# Arduino_PyunPyun.net
KiCad netlist of a schematic drawn in EAGLE
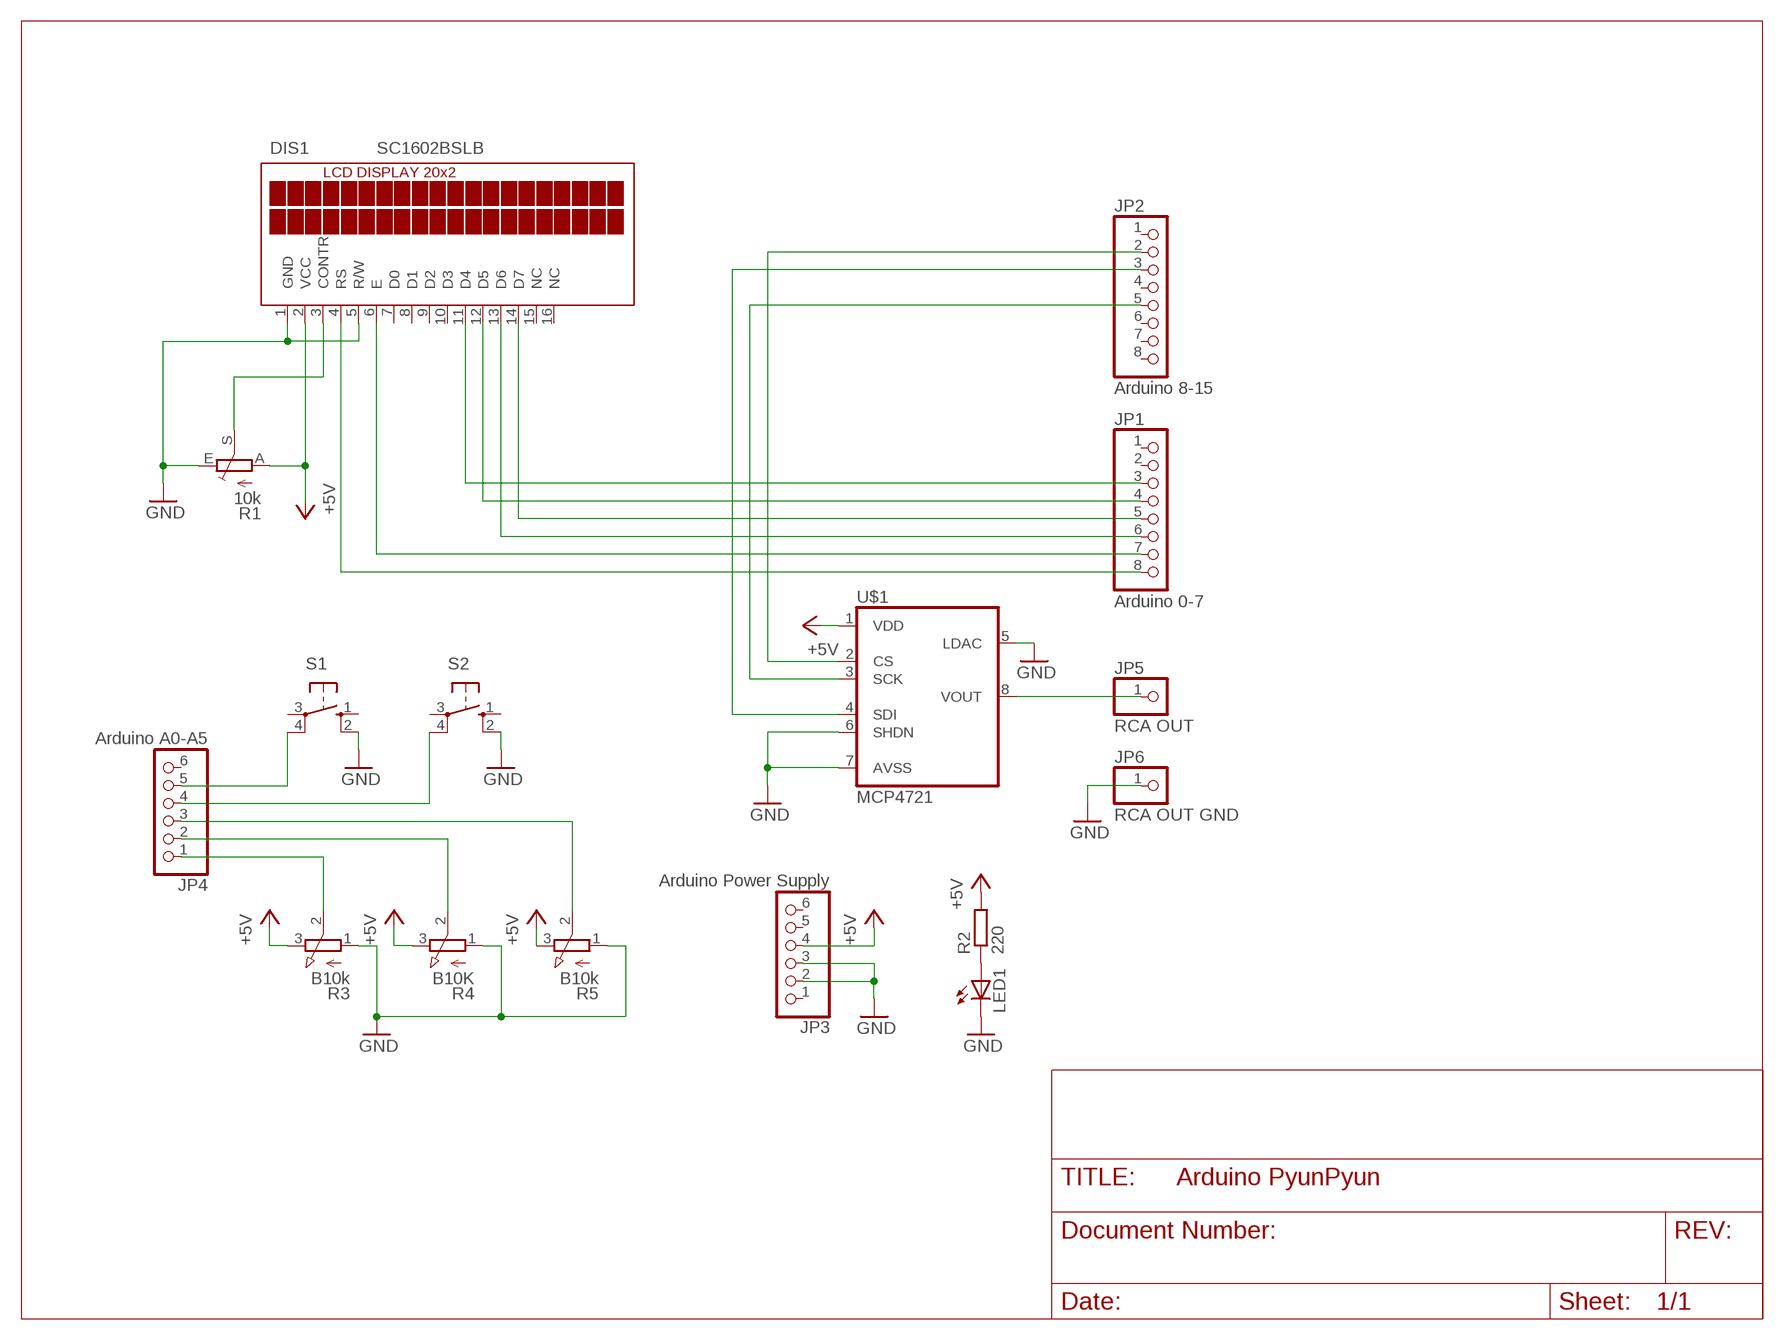
[diagram p0: schematic, sheet 1]

(export (version "E")
  (design (tool "Eeschema 10.0.6"))
  (components
    (comp (ref "DIS1")
      (value "SC1602BSLB")
      (footprint "eagle-import:TUXGR_20X2")
      (libsource (lib "eagle-import") (part "TUXGR_20X2"))
    )
    (comp (ref "JP1")
      (value "Arduino 0-7")
      (footprint "eagle-import:1X08")
      (libsource (lib "eagle-import") (part "PINHD-1X8"))
    )
    (comp (ref "JP2")
      (value "Arduino 8-15")
      (footprint "eagle-import:1X08")
      (libsource (lib "eagle-import") (part "PINHD-1X8"))
    )
    (comp (ref "JP3")
      (value "Arduino Power Supply")
      (footprint "eagle-import:1X06")
      (libsource (lib "eagle-import") (part "PINHD-1X6"))
    )
    (comp (ref "JP4")
      (value "Arduino A0-A5")
      (footprint "eagle-import:1X06")
      (libsource (lib "eagle-import") (part "PINHD-1X6"))
    )
    (comp (ref "JP5")
      (value "RCA OUT")
      (footprint "eagle-import:1X01")
      (libsource (lib "eagle-import") (part "PINHD-1X1"))
    )
    (comp (ref "JP6")
      (value "RCA OUT GND")
      (footprint "eagle-import:1X01")
      (libsource (lib "eagle-import") (part "PINHD-1X1"))
    )
    (comp (ref "LED1")
      (value "LED5MM")
      (footprint "eagle-import:LED5MM")
      (libsource (lib "eagle-import") (part "LED5MM"))
    )
    (comp (ref "R1")
      (value "10k")
      (footprint "eagle-import:B25P")
      (libsource (lib "eagle-import") (part "TRIM_EU-B25P"))
    )
    (comp (ref "R2")
      (value "220")
      (footprint "eagle-import:0207_7")
      (libsource (lib "eagle-import") (part "R-EU_0207/7"))
    )
    (comp (ref "R3")
      (value "B10k")
      (footprint "eagle-import:3RP_1610N")
      (libsource (lib "eagle-import") (part "3RP/1610N"))
    )
    (comp (ref "R4")
      (value "B10K")
      (footprint "eagle-import:3RP_1610N")
      (libsource (lib "eagle-import") (part "3RP/1610N"))
    )
    (comp (ref "R5")
      (value "B10k")
      (footprint "eagle-import:3RP_1610N")
      (libsource (lib "eagle-import") (part "3RP/1610N"))
    )
    (comp (ref "S1")
      (value "40-XX")
      (footprint "eagle-import:B3F-40XX")
      (fields (field (name "MF") "OMRON COMPONENTS USA") (field (name "MPN") "B3F-4000"))
      (libsource (lib "eagle-import") (part "40-XX"))
    )
    (comp (ref "S2")
      (value "40-XX")
      (footprint "eagle-import:B3F-40XX")
      (fields (field (name "MF") "OMRON COMPONENTS USA") (field (name "MPN") "B3F-4000"))
      (libsource (lib "eagle-import") (part "40-XX"))
    )
    (comp (ref "U$1")
      (value "MCP4721")
      (footprint "eagle-import:MCP4721")
      (libsource (lib "eagle-import") (part "MCP4721"))
    )
  )
  (nets
    (net (code "1") (name "+5V") (class "Default")
      (node (ref "DIS1") (pin "2") (pinfunction "VCC_2") (pintype "power_in"))
      (node (ref "JP3") (pin "4") (pinfunction "4_4") (pintype "passive"))
      (node (ref "R1") (pin "A") (pinfunction "A_A") (pintype "passive"))
      (node (ref "R2") (pin "2") (pinfunction "2_2") (pintype "passive"))
      (node (ref "R3") (pin "3") (pinfunction "E_3") (pintype "passive"))
      (node (ref "R4") (pin "3") (pinfunction "E_3") (pintype "passive"))
      (node (ref "R5") (pin "3") (pinfunction "E_3") (pintype "passive"))
      (node (ref "U$1") (pin "1") (pinfunction "VDD_1") (pintype "power_in"))
    )
    (net (code "2") (name "GND") (class "Default")
      (node (ref "DIS1") (pin "1") (pinfunction "GND_1") (pintype "power_in"))
      (node (ref "DIS1") (pin "5") (pinfunction "R/W_5") (pintype "input"))
      (node (ref "JP3") (pin "2") (pinfunction "2_2") (pintype "passive"))
      (node (ref "JP3") (pin "3") (pinfunction "3_3") (pintype "passive"))
      (node (ref "JP6") (pin "1") (pinfunction "1_1") (pintype "passive"))
      (node (ref "LED1") (pin "K") (pinfunction "C_K") (pintype "passive"))
      (node (ref "R1") (pin "E") (pinfunction "E_E") (pintype "passive"))
      (node (ref "R3") (pin "1") (pinfunction "A_1") (pintype "passive"))
      (node (ref "R4") (pin "1") (pinfunction "A_1") (pintype "passive"))
      (node (ref "R5") (pin "1") (pinfunction "A_1") (pintype "passive"))
      (node (ref "S1") (pin "2") (pinfunction "S1_2") (pintype "passive"))
      (node (ref "S2") (pin "2") (pinfunction "S1_2") (pintype "passive"))
      (node (ref "U$1") (pin "5") (pinfunction "LDAC_5") (pintype "input"))
      (node (ref "U$1") (pin "6") (pinfunction "SHDN_6") (pintype "input"))
      (node (ref "U$1") (pin "7") (pinfunction "AVSS_7") (pintype "power_in"))
    )
    (net (code "3") (name "Net-(DIS1-CONTR)") (class "Default")
      (node (ref "DIS1") (pin "3") (pinfunction "CONTR_3") (pintype "input"))
      (node (ref "R1") (pin "S") (pinfunction "S_S") (pintype "passive"))
    )
    (net (code "4") (name "Net-(DIS1-D4)") (class "Default")
      (node (ref "DIS1") (pin "11") (pinfunction "D4_11") (pintype "input"))
      (node (ref "JP1") (pin "3") (pinfunction "3_3") (pintype "passive"))
    )
    (net (code "5") (name "Net-(DIS1-D5)") (class "Default")
      (node (ref "DIS1") (pin "12") (pinfunction "D5_12") (pintype "input"))
      (node (ref "JP1") (pin "4") (pinfunction "4_4") (pintype "passive"))
    )
    (net (code "6") (name "Net-(DIS1-D6)") (class "Default")
      (node (ref "DIS1") (pin "13") (pinfunction "D6_13") (pintype "input"))
      (node (ref "JP1") (pin "6") (pinfunction "6_6") (pintype "passive"))
    )
    (net (code "7") (name "Net-(DIS1-D7)") (class "Default")
      (node (ref "DIS1") (pin "14") (pinfunction "D7_14") (pintype "input"))
      (node (ref "JP1") (pin "5") (pinfunction "5_5") (pintype "passive"))
    )
    (net (code "8") (name "Net-(DIS1-E)") (class "Default")
      (node (ref "DIS1") (pin "6") (pinfunction "E_6") (pintype "input"))
      (node (ref "JP1") (pin "7") (pinfunction "7_7") (pintype "passive"))
    )
    (net (code "9") (name "Net-(DIS1-RS)") (class "Default")
      (node (ref "DIS1") (pin "4") (pinfunction "RS_4") (pintype "input"))
      (node (ref "JP1") (pin "8") (pinfunction "8_8") (pintype "passive"))
    )
    (net (code "10") (name "Net-(LED1-PadA)") (class "Default")
      (node (ref "LED1") (pin "A") (pinfunction "A_A") (pintype "passive"))
      (node (ref "R2") (pin "1") (pinfunction "1_1") (pintype "passive"))
    )
    (net (code "11") (name "Net-(R3-S)") (class "Default")
      (node (ref "JP4") (pin "1") (pinfunction "1_1") (pintype "passive"))
      (node (ref "R3") (pin "2") (pinfunction "S_2") (pintype "passive"))
    )
    (net (code "12") (name "Net-(R4-S)") (class "Default")
      (node (ref "JP4") (pin "2") (pinfunction "2_2") (pintype "passive"))
      (node (ref "R4") (pin "2") (pinfunction "S_2") (pintype "passive"))
    )
    (net (code "13") (name "Net-(R5-S)") (class "Default")
      (node (ref "JP4") (pin "3") (pinfunction "3_3") (pintype "passive"))
      (node (ref "R5") (pin "2") (pinfunction "S_2") (pintype "passive"))
    )
    (net (code "14") (name "Net-(S1-P1)") (class "Default")
      (node (ref "JP4") (pin "5") (pinfunction "5_5") (pintype "passive"))
      (node (ref "S1") (pin "4") (pinfunction "P1_4") (pintype "passive"))
    )
    (net (code "15") (name "Net-(S2-P1)") (class "Default")
      (node (ref "JP4") (pin "4") (pinfunction "4_4") (pintype "passive"))
      (node (ref "S2") (pin "4") (pinfunction "P1_4") (pintype "passive"))
    )
    (net (code "16") (name "Net-(U$1-CS)") (class "Default")
      (node (ref "JP2") (pin "2") (pinfunction "2_2") (pintype "passive"))
      (node (ref "U$1") (pin "2") (pinfunction "CS_2") (pintype "input"))
    )
    (net (code "17") (name "Net-(U$1-SCK)") (class "Default")
      (node (ref "JP2") (pin "5") (pinfunction "5_5") (pintype "passive"))
      (node (ref "U$1") (pin "3") (pinfunction "SCK_3") (pintype "output"))
    )
    (net (code "18") (name "Net-(U$1-SDI)") (class "Default")
      (node (ref "JP2") (pin "3") (pinfunction "3_3") (pintype "passive"))
      (node (ref "U$1") (pin "4") (pinfunction "SDI_4") (pintype "input"))
    )
    (net (code "19") (name "Net-(U$1-VOUT)") (class "Default")
      (node (ref "JP5") (pin "1") (pinfunction "1_1") (pintype "passive"))
      (node (ref "U$1") (pin "8") (pinfunction "VOUT_8") (pintype "output"))
    )
    (net (code "20") (name "unconnected-(DIS1-D0-Pad7)") (class "Default")
      (node (ref "DIS1") (pin "7") (pinfunction "D0_7") (pintype "input"))
    )
    (net (code "21") (name "unconnected-(DIS1-D1-Pad8)") (class "Default")
      (node (ref "DIS1") (pin "8") (pinfunction "D1_8") (pintype "input"))
    )
    (net (code "22") (name "unconnected-(DIS1-D2-Pad9)") (class "Default")
      (node (ref "DIS1") (pin "9") (pinfunction "D2_9") (pintype "input"))
    )
    (net (code "23") (name "unconnected-(DIS1-D3-Pad10)") (class "Default")
      (node (ref "DIS1") (pin "10") (pinfunction "D3_10") (pintype "input"))
    )
    (net (code "24") (name "unconnected-(DIS1-NC-Pad15)") (class "Default")
      (node (ref "DIS1") (pin "15") (pinfunction "NC_15") (pintype "no_connect"))
    )
    (net (code "25") (name "unconnected-(DIS1-NC-Pad16)") (class "Default")
      (node (ref "DIS1") (pin "16") (pinfunction "NC_16") (pintype "no_connect"))
    )
    (net (code "26") (name "unconnected-(JP1-Pad1)") (class "Default")
      (node (ref "JP1") (pin "1") (pinfunction "1_1") (pintype "passive"))
    )
    (net (code "27") (name "unconnected-(JP1-Pad2)") (class "Default")
      (node (ref "JP1") (pin "2") (pinfunction "2_2") (pintype "passive"))
    )
    (net (code "28") (name "unconnected-(JP2-Pad1)") (class "Default")
      (node (ref "JP2") (pin "1") (pinfunction "1_1") (pintype "passive"))
    )
    (net (code "29") (name "unconnected-(JP2-Pad4)") (class "Default")
      (node (ref "JP2") (pin "4") (pinfunction "4_4") (pintype "passive"))
    )
    (net (code "30") (name "unconnected-(JP2-Pad6)") (class "Default")
      (node (ref "JP2") (pin "6") (pinfunction "6_6") (pintype "passive"))
    )
    (net (code "31") (name "unconnected-(JP2-Pad7)") (class "Default")
      (node (ref "JP2") (pin "7") (pinfunction "7_7") (pintype "passive"))
    )
    (net (code "32") (name "unconnected-(JP2-Pad8)") (class "Default")
      (node (ref "JP2") (pin "8") (pinfunction "8_8") (pintype "passive"))
    )
    (net (code "33") (name "unconnected-(JP3-Pad1)") (class "Default")
      (node (ref "JP3") (pin "1") (pinfunction "1_1") (pintype "passive"))
    )
    (net (code "34") (name "unconnected-(JP3-Pad5)") (class "Default")
      (node (ref "JP3") (pin "5") (pinfunction "5_5") (pintype "passive"))
    )
    (net (code "35") (name "unconnected-(JP3-Pad6)") (class "Default")
      (node (ref "JP3") (pin "6") (pinfunction "6_6") (pintype "passive"))
    )
    (net (code "36") (name "unconnected-(JP4-Pad6)") (class "Default")
      (node (ref "JP4") (pin "6") (pinfunction "6_6") (pintype "passive"))
    )
    (net (code "37") (name "unconnected-(S1-P-Pad3)") (class "Default")
      (node (ref "S1") (pin "3") (pinfunction "P_3") (pintype "passive"))
    )
    (net (code "38") (name "unconnected-(S1-S-Pad1)") (class "Default")
      (node (ref "S1") (pin "1") (pinfunction "S_1") (pintype "passive"))
    )
    (net (code "39") (name "unconnected-(S2-P-Pad3)") (class "Default")
      (node (ref "S2") (pin "3") (pinfunction "P_3") (pintype "passive"))
    )
    (net (code "40") (name "unconnected-(S2-S-Pad1)") (class "Default")
      (node (ref "S2") (pin "1") (pinfunction "S_1") (pintype "passive"))
    )
  )
)
